# Charger_Interface_-_Connectors.net
KiCad netlist of a schematic drawn in Altium Designer
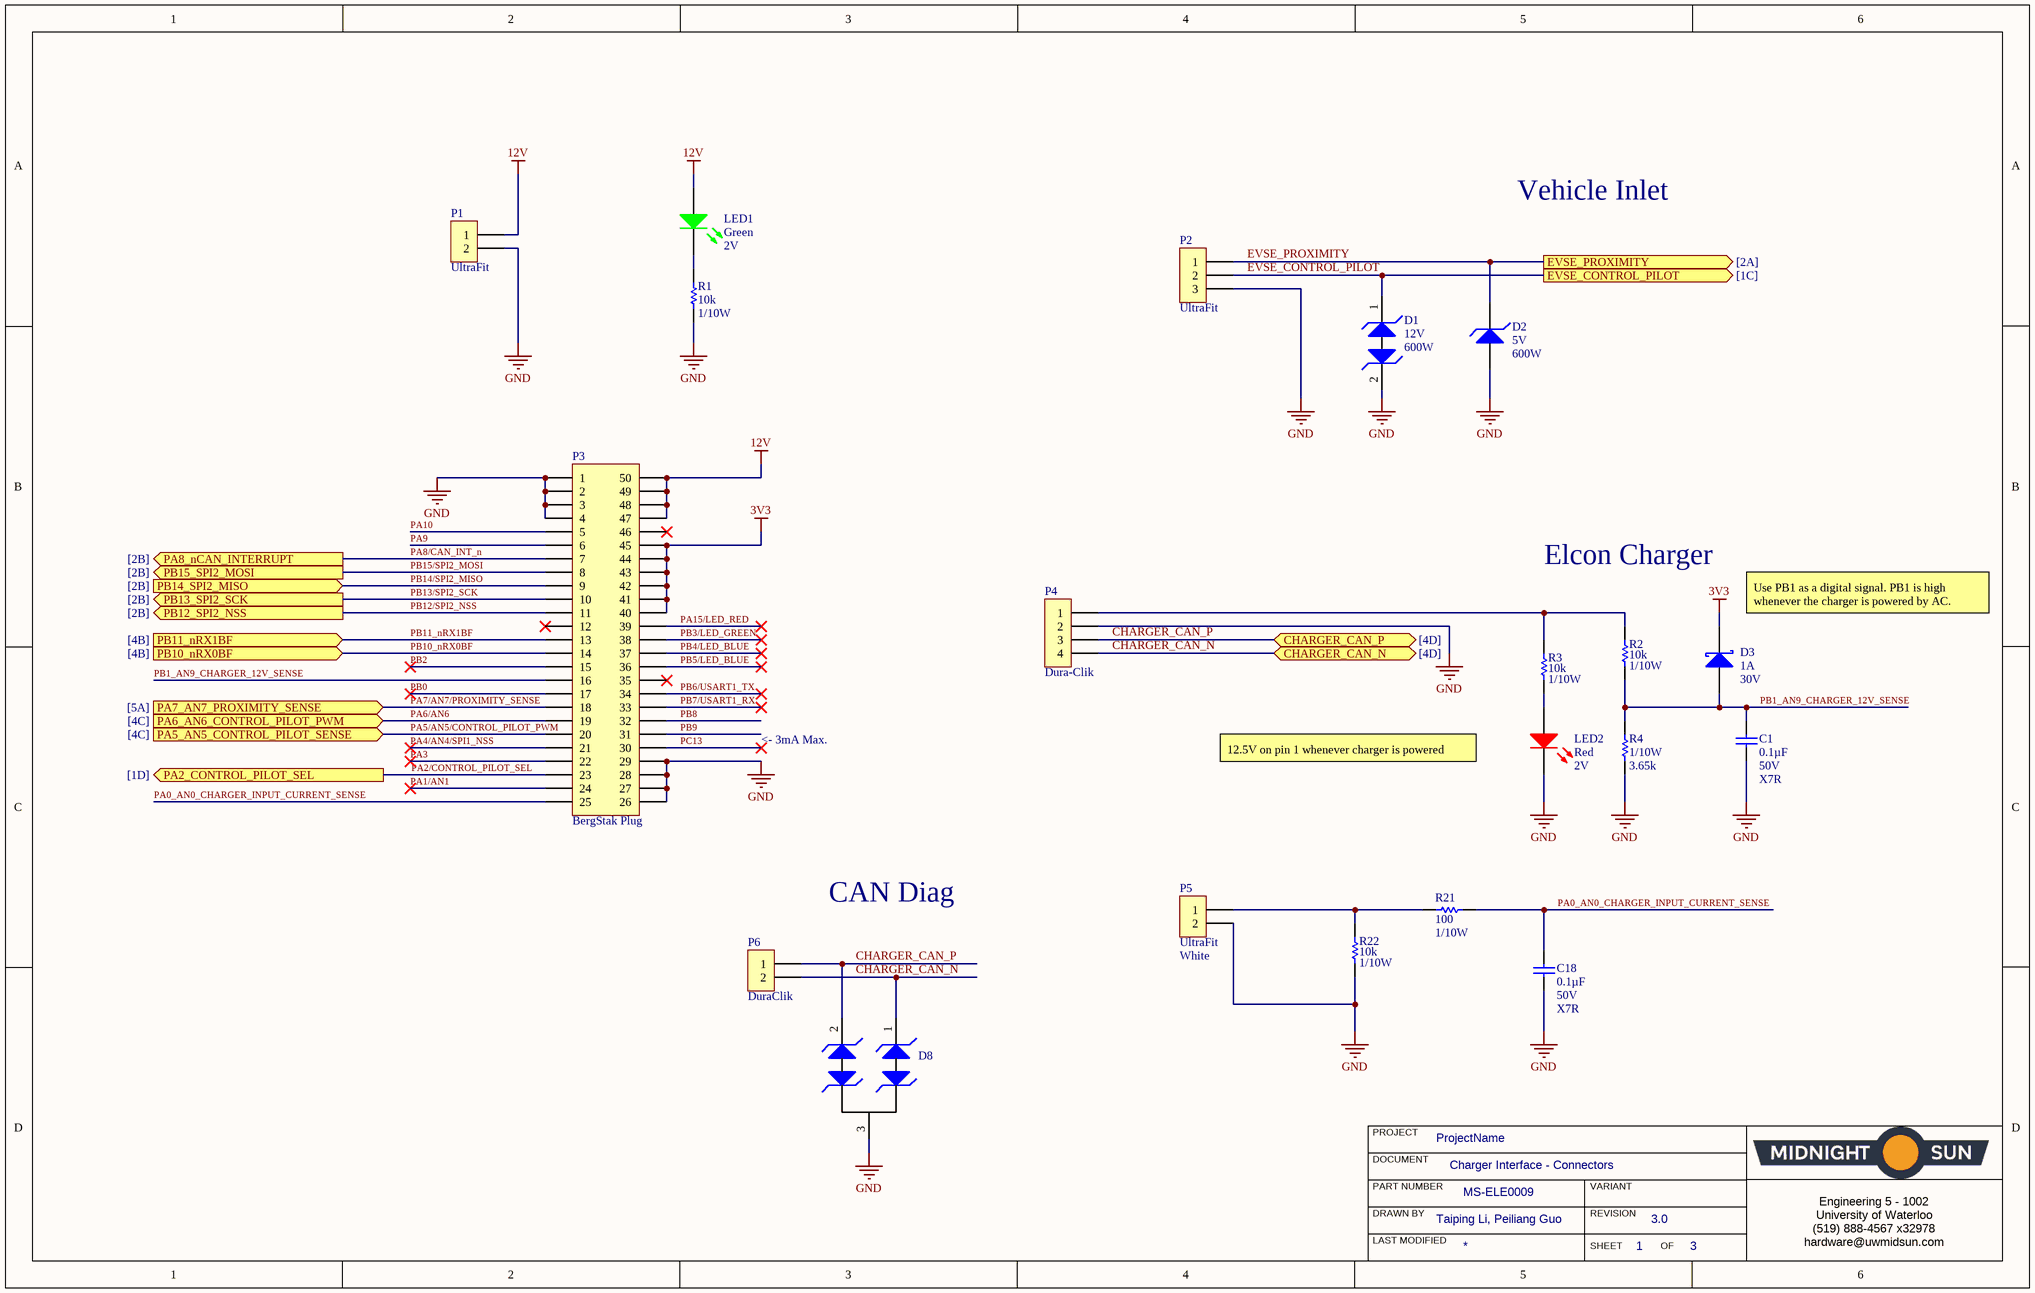
[diagram p0: Charger Interface - Connectors.SchDoc]

(export (version "E")
  (design (tool "Eeschema 10.0.6"))
  (components
    (comp (ref "C1")
      (value "CAP CER 0.1UF 50V 10% X7R 0603")
      (footprint "CAP, 0603")
      (description "0.10µF ±10% 50V Ceramic Capacitor X7R 0603 (1608 Metric)")
      (fields
        (field (name "TOLERANCE") "±10%")
        (field (name "CAPACITANCE") "0.1µF")
        (field (name "VOLTAGE") "50V")
        (field (name "TEMPERATURE COEFFICIENT") "X7R")
      )
      (libsource (lib "altium-import") (part "root_0_CAP CER 0.1UF 50V 10% X7R 0603_"))
    )
    (comp (ref "C18")
      (value "CAP CER 0.1UF 50V 10% X7R 0603")
      (footprint "CAP, 0603")
      (description "0.10µF ±10% 50V Ceramic Capacitor X7R 0603 (1608 Metric)")
      (fields
        (field (name "TOLERANCE") "±10%")
        (field (name "CAPACITANCE") "0.1µF")
        (field (name "VOLTAGE") "50V")
        (field (name "TEMPERATURE COEFFICIENT") "X7R")
      )
      (libsource (lib "Schematic Diagrams") (part "CAP CER 0.1UF 50V 10% X7R 0603"))
    )
    (comp (ref "D1")
      (value "DIODE TVS 12VWM 19.6VC DO-214AA (SMB)")
      (footprint "DO-214AA Diode")
      (description "TVS DIODE 12V 19.6V DO214AA")
      (fields
        (field (name "MANUFACTURER") "Vishay Semiconductor Diodes Division")
        (field (name "MANUFACTURER PART NUMBER") "SMBJ12CD-M3/H")
        (field (name "VOLTAGE - REVERSE STANDOFF (TYP)") "12V")
        (field (name "POWER - PEAK PULSE") "600W")
      )
      (libsource (lib "Schematic Diagrams") (part "DIODE TVS 12VWM 19.6VC DO-214AA (SMB)"))
    )
    (comp (ref "D2")
      (value "DIODE TVS 5VWM 9.1VC DO-214AA (SMB)")
      (footprint "DO-214AA Diode")
      (description "TVS DIODE 5V 9.1V DO214AA")
      (fields
        (field (name "MANUFACTURER") "Vishay Semiconductor Diodes Division")
        (field (name "MANUFACTURER PART NUMBER") "SMBJ5.0D-M3/H")
        (field (name "VOLTAGE - REVERSE STANDOFF (TYP)") "5V")
        (field (name "POWER - PEAK PULSE") "600W")
      )
      (libsource (lib "Schematic Diagrams") (part "DIODE TVS 5VWM 9.1VC DO-214AA (SMB)"))
    )
    (comp (ref "D3")
      (value "DIODE SCHOTTKY 30V 1A POWERDI123")
      (footprint "DIODE SCHOTTKY 30V 1A POWERDI123")
      (description "Diode Schottky 30V 1A Surface Mount PowerDI™ 123")
      (fields
        (field (name "MANUFACTURER") "Diodes Incorporated")
        (field (name "MANUFACTURER PART NUMBER") "DFLS130L-7")
        (field (name "CURRENT - AVERAGE RECTIFIED (IO)") "1A")
        (field (name "VOLTAGE - DC REVERSE (VR) (MAX)") "30V")
      )
      (libsource (lib "Schematic Diagrams") (part "DIODE SCHOTTKY 30V 1A POWERDI123"))
    )
    (comp (ref "D8")
      (value "DIODE TVS 24VWM 70VC SOT23")
      (footprint "MOSFET P-CH 30V 3.8A SOT-23")
      (description "TVS DIODE 24VWM 70VC SOT23")
      (libsource (lib "altium-import") (part "root_3_DIODE TVS 24VWM 70VC SOT23_"))
    )
    (comp (ref "LED1")
      (value "LED GREEN CLEAR 2V 0603")
      (footprint "LED_0603")
      (description "Green 572nm LED Indication - Discrete 2V 0603 (1608 Metric)")
      (fields
        (field (name "MANUFACTURER") "Wurth Electronics Inc.")
        (field (name "MANUFACTURER PART NUMBER") "150060VS75000")
        (field (name "COLOR") "Green")
        (field (name "VOLTAGE - FORWARD (VF) (TYP)") "2V")
      )
      (libsource (lib "Schematic Diagrams") (part "LED GREEN CLEAR 2V 0603"))
    )
    (comp (ref "LED2")
      (value "LED RED CLEAR 2V 0603")
      (footprint "LED_0603")
      (description "Red 631nm LED Indication - Discrete 2V 0603 (1608 Metric)")
      (fields
        (field (name "MANUFACTURER") "Wurth Electronics Inc.")
        (field (name "MANUFACTURER PART NUMBER") "150060RS75000")
        (field (name "COLOR") "Red")
        (field (name "VOLTAGE - FORWARD (VF) (TYP)") "2V")
      )
      (libsource (lib "altium-import") (part "root_3_LED RED CLEAR 2V 0603_"))
    )
    (comp (ref "P1")
      (value "CONN 2POS ULTRA-FIT 0.138\"")
      (footprint "CONN, 2POS ULTRA-FIT")
      (description "2 Positions Header, Shrouded Connector 0.138\" (3.50mm) Through Hole Gold")
      (fields (field (name "VOLTAGE") "400V") (field (name "SERIES") "UltraFit"))
      (libsource (lib "Schematic Diagrams") (part "CONN 2POS ULTRA-FIT 0.138{dblquote}"))
    )
    (comp (ref "P2")
      (value "CONN 3POS ULTRA-FIT 0.138\"")
      (footprint "CONN, 3POS ULTRA-FIT")
      (description "3 Positions Header Connector 0.138\" (3.50mm) Through Hole Tin")
      (fields (field (name "VOLTAGE") "400V") (field (name "SERIES") "UltraFit"))
      (libsource (lib "altium-import") (part "root_0_CONN 3POS ULTRA-FIT 0.138{dblquote}_"))
    )
    (comp (ref "P3")
      (value "CONN 50POS Bergstak Plug 0.02\"")
      (footprint "CONN, Bergstak 50 Pos Plug")
      (description "50 Position Connector Plug, Outer Shroud Contacts Surface Mount Gold")
      (fields (field (name "SERIES") "BergStak Plug"))
      (libsource (lib "Schematic Diagrams") (part "CONN 50POS Bergstak Plug 0.02{dblquote}"))
    )
    (comp (ref "P4")
      (value "Dura-Clik")
      (footprint "CONN, 4POS DURA-CLIK VERT")
      (description "4 Positions Header Connector 0.079\" (2.00mm) Surface Mount Tin")
      (fields
        (field (name "MANUFACTURER") "Molex, LLC")
        (field (name "MANUFACTURER PART NUMBER") "5600200420")
      )
      (libsource (lib "Schematic Diagrams") (part "CONN 4POS DURA-CLIK 0.079{dblquote}"))
    )
    (comp (ref "P5")
      (value "CONN 2POS ULTRA-FIT NATURAL COLOR 0.138\"")
      (footprint "CONN, 2POS ULTRA-FIT - NATURAL COLOR")
      (description "2 Positions Header, Shrouded Connector 0.138\" (3.50mm) Through Hole")
      (fields
        (field (name "VOLTAGE") "400V")
        (field (name "SERIES") "UltraFit")
        (field (name "COLOR") "White")
      )
      (libsource (lib "altium-import") (part "root_0_CONN 2POS ULTRA-FIT NATURAL COLOR 0.138{dblquote}_"))
    )
    (comp (ref "P6")
      (value "CONN 2POS DURA-CLIK 0.079\"")
      (footprint "CONN, 2POS Dura-Click")
      (description "2 Positions Header, Shrouded Connector 0.079\" (2.00mm) Surface Mount, Right Angle Tin")
      (fields (field (name "SERIES") "DuraClik"))
      (libsource (lib "altium-import") (part "root_0_CONN 2POS DURA-CLIK 0.079{dblquote}_"))
    )
    (comp (ref "R1")
      (value "RES 10K OHM 1% 1/10W 0603")
      (footprint "RES, 0603")
      (description "RES SMD 10K OHM 1% 1/10W 0603")
      (fields
        (field (name "TOLERANCE") "±1%")
        (field (name "RESISTANCE") "10k")
        (field (name "POWER") "1/10W")
      )
      (libsource (lib "Schematic Diagrams") (part "RES 10K OHM 1% 1/10W 0603"))
    )
    (comp (ref "R2")
      (value "RES 10K OHM 1% 1/10W 0603")
      (footprint "RES, 0603")
      (description "RES SMD 10K OHM 1% 1/10W 0603")
      (fields
        (field (name "TOLERANCE") "±1%")
        (field (name "RESISTANCE") "10k")
        (field (name "POWER") "1/10W")
      )
      (libsource (lib "Schematic Diagrams") (part "RES 10K OHM 1% 1/10W 0603"))
    )
    (comp (ref "R3")
      (value "RES 10K OHM 1% 1/10W 0603")
      (footprint "RES, 0603")
      (description "RES SMD 10K OHM 1% 1/10W 0603")
      (fields
        (field (name "TOLERANCE") "±1%")
        (field (name "RESISTANCE") "10k")
        (field (name "POWER") "1/10W")
      )
      (libsource (lib "Schematic Diagrams") (part "RES 10K OHM 1% 1/10W 0603"))
    )
    (comp (ref "R4")
      (value "RES 3.65K OHM 0.1% 1/10W 0603")
      (footprint "RES, 0603")
      (description "3.65 kOhms ±0.1% 0.1W, 1/10W Chip Resistor 0603 (1608 Metric) Automotive AEC-Q200 Thin Film")
      (fields
        (field (name "MANUFACTURER") "Panasonic")
        (field (name "MANUFACTURER PART NUMBER") "ERA3AEB3651V")
        (field (name "POWER RATING") "1/10W")
        (field (name "RESISTANCE") "3.65k")
      )
      (libsource (lib "Schematic Diagrams") (part "RES 3.65K OHM 0.1% 1/10W 0603"))
    )
    (comp (ref "R21")
      (value "RES 100 OHM 1% 1/10W 0603")
      (footprint "RES, 0603")
      (description "100 Ohm ±1% 0.1W, 1/10W Chip Resistor 0603 (1608 Metric) Moisture Resistant Thick Film")
      (fields
        (field (name "TOLERANCE") "±1%")
        (field (name "RESISTANCE") "100")
        (field (name "POWER") "1/10W")
      )
      (libsource (lib "Schematic Diagrams") (part "RES 100 OHM 1% 1/10W 0603"))
    )
    (comp (ref "R22")
      (value "RES 10K OHM 1% 1/10W 0603")
      (footprint "RES, 0603")
      (description "RES SMD 10K OHM 1% 1/10W 0603")
      (fields
        (field (name "TOLERANCE") "±1%")
        (field (name "RESISTANCE") "10k")
        (field (name "POWER") "1/10W")
      )
      (libsource (lib "Schematic Diagrams") (part "RES 10K OHM 1% 1/10W 0603"))
    )
  )
  (nets
    (net (code "1") (name "/CHARGER_CAN_N") (class "Default")
      (node (ref "D8") (pin "1") (pinfunction "Cathode1_1") (pintype "passive"))
      (node (ref "P4") (pin "4") (pinfunction "4_4") (pintype "passive"))
      (node (ref "P6") (pin "2") (pinfunction "2_2") (pintype "passive"))
    )
    (net (code "2") (name "/CHARGER_CAN_P") (class "Default")
      (node (ref "D8") (pin "2") (pinfunction "Cathode2_2") (pintype "passive"))
      (node (ref "P4") (pin "3") (pinfunction "3_3") (pintype "passive"))
      (node (ref "P6") (pin "1") (pinfunction "1_1") (pintype "passive"))
    )
    (net (code "3") (name "/EVSE_CONTROL_PILOT") (class "Default")
      (node (ref "D1") (pin "1") (pinfunction "Cathode1_1") (pintype "passive"))
      (node (ref "P2") (pin "2") (pinfunction "2_2") (pintype "passive"))
    )
    (net (code "4") (name "/EVSE_PROXIMITY") (class "Default")
      (node (ref "D2") (pin "2") (pinfunction "2_2") (pintype "passive"))
      (node (ref "P2") (pin "1") (pinfunction "1_1") (pintype "passive"))
    )
    (net (code "5") (name "/PA0_AN0_CHARGER_INPUT_CURRENT_SENSE") (class "Default")
      (node (ref "C18") (pin "1") (pinfunction "1_1") (pintype "passive"))
      (node (ref "P3") (pin "25") (pinfunction "25_25") (pintype "passive"))
      (node (ref "R21") (pin "2") (pinfunction "2_2") (pintype "passive"))
    )
    (net (code "6") (name "/PA1{slash}AN1") (class "Default")
      (node (ref "P3") (pin "24") (pinfunction "24_24") (pintype "passive+no_connect"))
    )
    (net (code "7") (name "/PA2{slash}CONTROL_PILOT_SEL") (class "Default")
      (node (ref "P3") (pin "23") (pinfunction "23_23") (pintype "passive"))
    )
    (net (code "8") (name "/PA3") (class "Default")
      (node (ref "P3") (pin "22") (pinfunction "22_22") (pintype "passive+no_connect"))
    )
    (net (code "9") (name "/PA4{slash}AN4{slash}SPI1_NSS") (class "Default")
      (node (ref "P3") (pin "21") (pinfunction "21_21") (pintype "passive+no_connect"))
    )
    (net (code "10") (name "/PA5{slash}AN5{slash}CONTROL_PILOT_PWM") (class "Default")
      (node (ref "P3") (pin "20") (pinfunction "20_20") (pintype "passive"))
    )
    (net (code "11") (name "/PA6{slash}AN6") (class "Default")
      (node (ref "P3") (pin "19") (pinfunction "19_19") (pintype "passive"))
    )
    (net (code "12") (name "/PA7{slash}AN7{slash}PROXIMITY_SENSE") (class "Default")
      (node (ref "P3") (pin "18") (pinfunction "18_18") (pintype "passive"))
    )
    (net (code "13") (name "/PA8{slash}CAN_INT_n") (class "Default")
      (node (ref "P3") (pin "7") (pinfunction "7_7") (pintype "passive"))
    )
    (net (code "14") (name "/PA9") (class "Default")
      (node (ref "P3") (pin "6") (pinfunction "6_6") (pintype "passive"))
    )
    (net (code "15") (name "/PA10") (class "Default")
      (node (ref "P3") (pin "5") (pinfunction "5_5") (pintype "passive"))
    )
    (net (code "16") (name "/PA15{slash}LED_RED") (class "Default")
      (node (ref "P3") (pin "39") (pinfunction "39_39") (pintype "passive+no_connect"))
    )
    (net (code "17") (name "/PB0") (class "Default")
      (node (ref "P3") (pin "17") (pinfunction "17_17") (pintype "passive+no_connect"))
    )
    (net (code "18") (name "/PB1_AN9_CHARGER_12V_SENSE") (class "Default")
      (node (ref "C1") (pin "1") (pinfunction "1_1") (pintype "passive"))
      (node (ref "D3") (pin "1") (pinfunction "A_1") (pintype "passive"))
      (node (ref "P3") (pin "16") (pinfunction "16_16") (pintype "passive"))
      (node (ref "R2") (pin "2") (pinfunction "2_2") (pintype "passive"))
      (node (ref "R4") (pin "1") (pinfunction "1_1") (pintype "passive"))
    )
    (net (code "19") (name "/PB2") (class "Default")
      (node (ref "P3") (pin "15") (pinfunction "15_15") (pintype "passive+no_connect"))
    )
    (net (code "20") (name "/PB3{slash}LED_GREEN") (class "Default")
      (node (ref "P3") (pin "38") (pinfunction "38_38") (pintype "passive+no_connect"))
    )
    (net (code "21") (name "/PB4{slash}LED_BLUE") (class "Default")
      (node (ref "P3") (pin "37") (pinfunction "37_37") (pintype "passive+no_connect"))
    )
    (net (code "22") (name "/PB5{slash}LED_BLUE") (class "Default")
      (node (ref "P3") (pin "36") (pinfunction "36_36") (pintype "passive+no_connect"))
    )
    (net (code "23") (name "/PB6{slash}USART1_TX") (class "Default")
      (node (ref "P3") (pin "34") (pinfunction "34_34") (pintype "passive+no_connect"))
    )
    (net (code "24") (name "/PB7{slash}USART1_RX") (class "Default")
      (node (ref "P3") (pin "33") (pinfunction "33_33") (pintype "passive+no_connect"))
    )
    (net (code "25") (name "/PB8") (class "Default")
      (node (ref "P3") (pin "32") (pinfunction "32_32") (pintype "passive"))
    )
    (net (code "26") (name "/PB9") (class "Default")
      (node (ref "P3") (pin "31") (pinfunction "31_31") (pintype "passive"))
    )
    (net (code "27") (name "/PB10_nRX0BF") (class "Default")
      (node (ref "P3") (pin "14") (pinfunction "14_14") (pintype "passive"))
    )
    (net (code "28") (name "/PB11_nRX1BF") (class "Default")
      (node (ref "P3") (pin "13") (pinfunction "13_13") (pintype "passive"))
    )
    (net (code "29") (name "/PB12{slash}SPI2_NSS") (class "Default")
      (node (ref "P3") (pin "11") (pinfunction "11_11") (pintype "passive"))
    )
    (net (code "30") (name "/PB13{slash}SPI2_SCK") (class "Default")
      (node (ref "P3") (pin "10") (pinfunction "10_10") (pintype "passive"))
    )
    (net (code "31") (name "/PB14{slash}SPI2_MISO") (class "Default")
      (node (ref "P3") (pin "9") (pinfunction "9_9") (pintype "passive"))
    )
    (net (code "32") (name "/PB15{slash}SPI2_MOSI") (class "Default")
      (node (ref "P3") (pin "8") (pinfunction "8_8") (pintype "passive"))
    )
    (net (code "33") (name "/PC13") (class "Default")
      (node (ref "P3") (pin "30") (pinfunction "30_30") (pintype "passive+no_connect"))
    )
    (net (code "34") (name "3V3") (class "Default")
      (node (ref "D3") (pin "2") (pinfunction "K_2") (pintype "passive"))
      (node (ref "P3") (pin "40") (pinfunction "40_40") (pintype "passive"))
      (node (ref "P3") (pin "41") (pinfunction "41_41") (pintype "passive"))
      (node (ref "P3") (pin "42") (pinfunction "42_42") (pintype "passive"))
      (node (ref "P3") (pin "43") (pinfunction "43_43") (pintype "passive"))
      (node (ref "P3") (pin "44") (pinfunction "44_44") (pintype "passive"))
      (node (ref "P3") (pin "45") (pinfunction "45_45") (pintype "passive"))
    )
    (net (code "35") (name "12V") (class "Default")
      (node (ref "LED1") (pin "1") (pinfunction "A_1") (pintype "passive"))
      (node (ref "P1") (pin "1") (pinfunction "1_1") (pintype "passive"))
      (node (ref "P3") (pin "47") (pinfunction "47_47") (pintype "passive"))
      (node (ref "P3") (pin "48") (pinfunction "48_48") (pintype "passive"))
      (node (ref "P3") (pin "49") (pinfunction "49_49") (pintype "passive"))
      (node (ref "P3") (pin "50") (pinfunction "50_50") (pintype "passive"))
    )
    (net (code "36") (name "GND") (class "Default")
      (node (ref "C1") (pin "2") (pinfunction "2_2") (pintype "passive"))
      (node (ref "C18") (pin "2") (pinfunction "2_2") (pintype "passive"))
      (node (ref "D1") (pin "2") (pinfunction "Cathode2_2") (pintype "passive"))
      (node (ref "D2") (pin "1") (pinfunction "1_1") (pintype "passive"))
      (node (ref "D8") (pin "3") (pinfunction "Common_Cathode_3") (pintype "power_in"))
      (node (ref "LED2") (pin "2") (pinfunction "K_2") (pintype "passive"))
      (node (ref "P1") (pin "2") (pinfunction "2_2") (pintype "passive"))
      (node (ref "P2") (pin "3") (pinfunction "3_3") (pintype "passive"))
      (node (ref "P3") (pin "1") (pinfunction "1_1") (pintype "passive"))
      (node (ref "P3") (pin "2") (pinfunction "2_2") (pintype "passive"))
      (node (ref "P3") (pin "26") (pinfunction "26_26") (pintype "passive"))
      (node (ref "P3") (pin "27") (pinfunction "27_27") (pintype "passive"))
      (node (ref "P3") (pin "28") (pinfunction "28_28") (pintype "passive"))
      (node (ref "P3") (pin "29") (pinfunction "29_29") (pintype "passive"))
      (node (ref "P3") (pin "3") (pinfunction "3_3") (pintype "passive"))
      (node (ref "P3") (pin "4") (pinfunction "4_4") (pintype "passive"))
      (node (ref "P4") (pin "2") (pinfunction "2_2") (pintype "passive"))
      (node (ref "P5") (pin "2") (pinfunction "2_2") (pintype "passive"))
      (node (ref "R1") (pin "2") (pinfunction "2_2") (pintype "passive"))
      (node (ref "R22") (pin "2") (pinfunction "2_2") (pintype "passive"))
      (node (ref "R4") (pin "2") (pinfunction "2_2") (pintype "passive"))
    )
    (net (code "37") (name "Net-(LED1-K)") (class "Default")
      (node (ref "LED1") (pin "2") (pinfunction "K_2") (pintype "passive"))
      (node (ref "R1") (pin "1") (pinfunction "1_1") (pintype "passive"))
    )
    (net (code "38") (name "Net-(LED2-A)") (class "Default")
      (node (ref "LED2") (pin "1") (pinfunction "A_1") (pintype "passive"))
      (node (ref "R3") (pin "2") (pinfunction "2_2") (pintype "passive"))
    )
    (net (code "39") (name "Net-(P4-Pad1)") (class "Default")
      (node (ref "P4") (pin "1") (pinfunction "1_1") (pintype "passive"))
      (node (ref "R2") (pin "1") (pinfunction "1_1") (pintype "passive"))
      (node (ref "R3") (pin "1") (pinfunction "1_1") (pintype "passive"))
    )
    (net (code "40") (name "Net-(P5-Pad1)") (class "Default")
      (node (ref "P5") (pin "1") (pinfunction "1_1") (pintype "passive"))
      (node (ref "R21") (pin "1") (pinfunction "1_1") (pintype "passive"))
      (node (ref "R22") (pin "1") (pinfunction "1_1") (pintype "passive"))
    )
    (net (code "41") (name "unconnected-(P3-Pad12)") (class "Default")
      (node (ref "P3") (pin "12") (pinfunction "12_12") (pintype "passive+no_connect"))
    )
    (net (code "42") (name "unconnected-(P3-Pad35)") (class "Default")
      (node (ref "P3") (pin "35") (pinfunction "35_35") (pintype "passive+no_connect"))
    )
    (net (code "43") (name "unconnected-(P3-Pad46)") (class "Default")
      (node (ref "P3") (pin "46") (pinfunction "46_46") (pintype "passive+no_connect"))
    )
  )
)
